# Tinyputer_IFC.net
KiCad netlist of a schematic drawn in Altium Designer
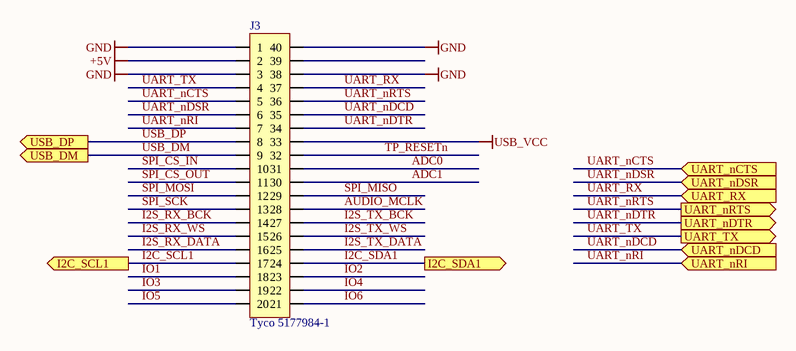
[diagram p0: Tinyputer_IFC.SchDoc]

(export (version "E")
  (design (tool "Eeschema 10.0.6"))
  (components
    (comp (ref "J3")
      (value "Tyco 5177984-1")
      (footprint "TYCO_5177984-1")
      (description "0.8 mm dual row")
      (libsource (lib "LIBRARY_SCH") (part "CON_2x20_PLUG_0.8_Tyco"))
    )
  )
  (nets
    (net (code "1") (name "+5V") (class "Default")
      (node (ref "J3") (pin "2") (pinfunction "2_2") (pintype "passive"))
    )
    (net (code "2") (name "/ADC0") (class "Default")
      (node (ref "J3") (pin "31") (pinfunction "31_31") (pintype "passive"))
    )
    (net (code "3") (name "/ADC1") (class "Default")
      (node (ref "J3") (pin "30") (pinfunction "30_30") (pintype "passive"))
    )
    (net (code "4") (name "/AUDIO_MCLK") (class "Default")
      (node (ref "J3") (pin "28") (pinfunction "28_28") (pintype "passive"))
    )
    (net (code "5") (name "/I2C_SCL1") (class "Default")
      (node (ref "J3") (pin "17") (pinfunction "17_17") (pintype "passive"))
    )
    (net (code "6") (name "/I2C_SDA1") (class "Default")
      (node (ref "J3") (pin "24") (pinfunction "24_24") (pintype "passive"))
    )
    (net (code "7") (name "/I2S_RX_BCK") (class "Default")
      (node (ref "J3") (pin "14") (pinfunction "14_14") (pintype "passive"))
    )
    (net (code "8") (name "/I2S_RX_DATA") (class "Default")
      (node (ref "J3") (pin "16") (pinfunction "16_16") (pintype "passive"))
    )
    (net (code "9") (name "/I2S_RX_WS") (class "Default")
      (node (ref "J3") (pin "15") (pinfunction "15_15") (pintype "passive"))
    )
    (net (code "10") (name "/I2S_TX_BCK") (class "Default")
      (node (ref "J3") (pin "27") (pinfunction "27_27") (pintype "passive"))
    )
    (net (code "11") (name "/I2S_TX_DATA") (class "Default")
      (node (ref "J3") (pin "25") (pinfunction "25_25") (pintype "passive"))
    )
    (net (code "12") (name "/I2S_TX_WS") (class "Default")
      (node (ref "J3") (pin "26") (pinfunction "26_26") (pintype "passive"))
    )
    (net (code "13") (name "/IO1") (class "Default")
      (node (ref "J3") (pin "18") (pinfunction "18_18") (pintype "passive"))
    )
    (net (code "14") (name "/IO2") (class "Default")
      (node (ref "J3") (pin "23") (pinfunction "23_23") (pintype "passive"))
    )
    (net (code "15") (name "/IO3") (class "Default")
      (node (ref "J3") (pin "19") (pinfunction "19_19") (pintype "passive"))
    )
    (net (code "16") (name "/IO4") (class "Default")
      (node (ref "J3") (pin "22") (pinfunction "22_22") (pintype "passive"))
    )
    (net (code "17") (name "/IO5") (class "Default")
      (node (ref "J3") (pin "20") (pinfunction "20_20") (pintype "passive"))
    )
    (net (code "18") (name "/IO6") (class "Default")
      (node (ref "J3") (pin "21") (pinfunction "21_21") (pintype "passive"))
    )
    (net (code "19") (name "/SPI_CS_IN") (class "Default")
      (node (ref "J3") (pin "10") (pinfunction "10_10") (pintype "passive"))
    )
    (net (code "20") (name "/SPI_CS_OUT") (class "Default")
      (node (ref "J3") (pin "11") (pinfunction "11_11") (pintype "passive"))
    )
    (net (code "21") (name "/SPI_MISO") (class "Default")
      (node (ref "J3") (pin "29") (pinfunction "29_29") (pintype "passive"))
    )
    (net (code "22") (name "/SPI_MOSI") (class "Default")
      (node (ref "J3") (pin "12") (pinfunction "12_12") (pintype "passive"))
    )
    (net (code "23") (name "/SPI_SCK") (class "Default")
      (node (ref "J3") (pin "13") (pinfunction "13_13") (pintype "passive"))
    )
    (net (code "24") (name "/TP_RESETn") (class "Default")
      (node (ref "J3") (pin "32") (pinfunction "32_32") (pintype "passive"))
    )
    (net (code "25") (name "/UART_RX") (class "Default")
      (node (ref "J3") (pin "37") (pinfunction "37_37") (pintype "passive"))
    )
    (net (code "26") (name "/UART_TX") (class "Default")
      (node (ref "J3") (pin "4") (pinfunction "4_4") (pintype "passive"))
    )
    (net (code "27") (name "/UART_nCTS") (class "Default")
      (node (ref "J3") (pin "5") (pinfunction "5_5") (pintype "passive"))
    )
    (net (code "28") (name "/UART_nDCD") (class "Default")
      (node (ref "J3") (pin "35") (pinfunction "35_35") (pintype "passive"))
    )
    (net (code "29") (name "/UART_nDSR") (class "Default")
      (node (ref "J3") (pin "6") (pinfunction "6_6") (pintype "passive"))
    )
    (net (code "30") (name "/UART_nDTR") (class "Default")
      (node (ref "J3") (pin "34") (pinfunction "34_34") (pintype "passive"))
    )
    (net (code "31") (name "/UART_nRI") (class "Default")
      (node (ref "J3") (pin "7") (pinfunction "7_7") (pintype "passive"))
    )
    (net (code "32") (name "/UART_nRTS") (class "Default")
      (node (ref "J3") (pin "36") (pinfunction "36_36") (pintype "passive"))
    )
    (net (code "33") (name "/USB_DM") (class "Default")
      (node (ref "J3") (pin "9") (pinfunction "9_9") (pintype "passive"))
    )
    (net (code "34") (name "/USB_DP") (class "Default")
      (node (ref "J3") (pin "8") (pinfunction "8_8") (pintype "passive"))
    )
    (net (code "35") (name "GND") (class "Default")
      (node (ref "J3") (pin "1") (pinfunction "1_1") (pintype "passive"))
      (node (ref "J3") (pin "3") (pinfunction "3_3") (pintype "passive"))
      (node (ref "J3") (pin "38") (pinfunction "38_38") (pintype "passive"))
      (node (ref "J3") (pin "40") (pinfunction "40_40") (pintype "passive"))
    )
    (net (code "36") (name "USB_VCC") (class "Default")
      (node (ref "J3") (pin "33") (pinfunction "33_33") (pintype "passive"))
    )
    (net (code "37") (name "unconnected-(J3-Pad39)") (class "Default")
      (node (ref "J3") (pin "39") (pinfunction "39_39") (pintype "passive"))
    )
  )
)
